# SCH.net
KiCad netlist of a schematic drawn in EasyEDA
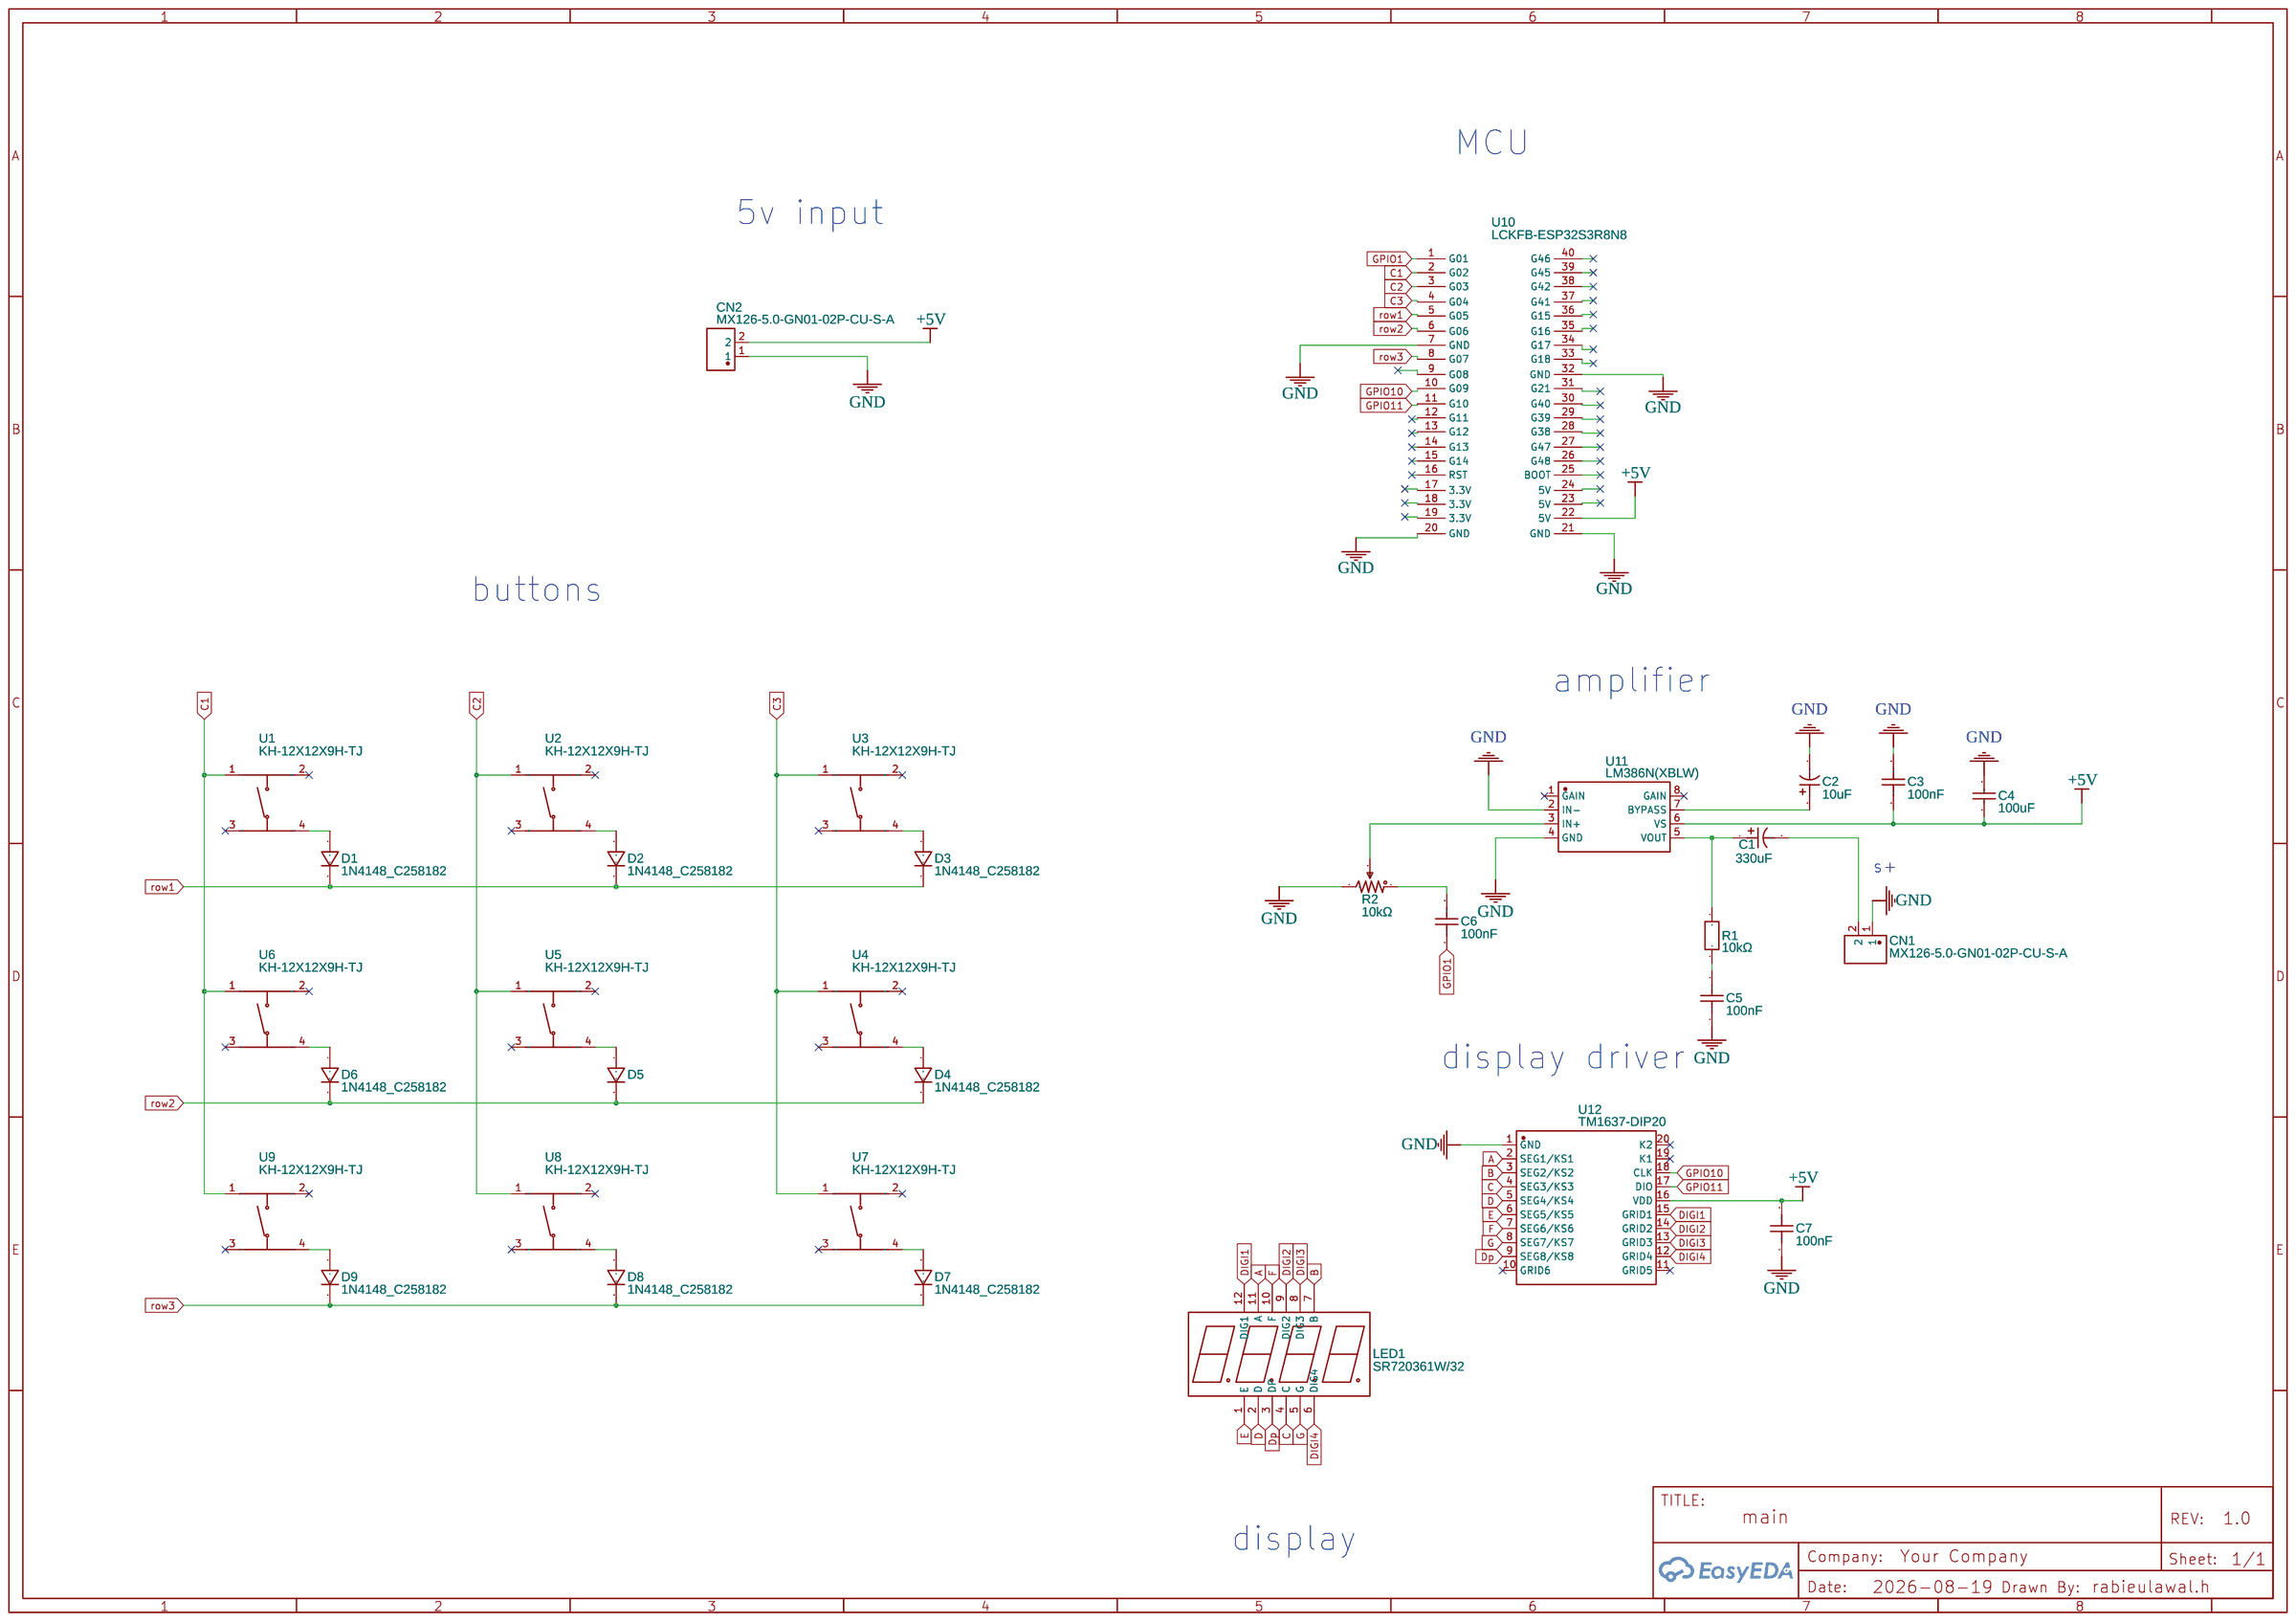
[diagram p0: schematic sheet]

(export (version "E")
  (design (tool "Eeschema 10.0.6"))
  (components
    (comp (ref "C1")
      (value "330uF")
      (fields
        (field (name "Manufacturer Part") "330uF10V6.3x11GF")
        (field (name "Manufacturer") "Econd(米朗电子)")
      )
      (libsource (lib "") (part "330UF10V6.3X11GF"))
    )
    (comp (ref "C2")
      (value "10uF")
      (fields (field (name "Manufacturer Part") "CG100ME511BP") (field (name "Manufacturer") "TWBOR(伯鸿)"))
      (libsource (lib "") (part "CG100ME511BP"))
    )
    (comp (ref "C3")
      (value "100nF")
      (fields (field (name "Manufacturer Part") "FM32X104K101EMG") (field (name "Manufacturer") "PSA(信昌电陶)"))
      (libsource (lib "") (part "FM32X104K101EMG"))
    )
    (comp (ref "C4")
      (value "100uF")
      (fields
        (field (name "Manufacturer Part") "CL32A107MQVNNNE")
        (field (name "Manufacturer") "SAMSUNG(三星)")
      )
      (libsource (lib "") (part "CL32A107MQVNNNE"))
    )
    (comp (ref "C5")
      (value "100nF")
      (fields (field (name "Manufacturer Part") "FM32X104K101EMG") (field (name "Manufacturer") "PSA(信昌电陶)"))
      (libsource (lib "") (part "FM32X104K101EMG"))
    )
    (comp (ref "C6")
      (value "100nF")
      (fields (field (name "Manufacturer Part") "FM32X104K101EMG") (field (name "Manufacturer") "PSA(信昌电陶)"))
      (libsource (lib "") (part "FM32X104K101EMG"))
    )
    (comp (ref "C7")
      (value "100nF")
      (fields (field (name "Manufacturer Part") "FM32X104K101EMG") (field (name "Manufacturer") "PSA(信昌电陶)"))
      (libsource (lib "") (part "FM32X104K101EMG"))
    )
    (comp (ref "CN1")
      (value "MX126-5.0-GN01-02P-CU-S-A")
      (fields
        (field (name "Manufacturer Part") "MX126-5.0-02P-GN01-Cu-S-A")
        (field (name "Manufacturer") "MAX(迈旭)")
      )
      (libsource (lib "") (part "MX126-5.0-GN01-02P-CU-S-A"))
    )
    (comp (ref "CN2")
      (value "MX126-5.0-GN01-02P-CU-S-A")
      (fields
        (field (name "Manufacturer Part") "MX126-5.0-02P-GN01-Cu-S-A")
        (field (name "Manufacturer") "MAX(迈旭)")
      )
      (libsource (lib "") (part "MX126-5.0-GN01-02P-CU-S-A_1"))
    )
    (comp (ref "D1")
      (value "1N4148_C258182")
      (fields (field (name "Manufacturer Part") "1N4148") (field (name "Manufacturer") "onsemi(安森美)"))
      (libsource (lib "") (part "1N4148_C258182"))
    )
    (comp (ref "D2")
      (value "1N4148_C258182")
      (fields (field (name "Manufacturer Part") "1N4148") (field (name "Manufacturer") "onsemi(安森美)"))
      (libsource (lib "") (part "1N4148_C258182"))
    )
    (comp (ref "D3")
      (value "1N4148_C258182")
      (fields (field (name "Manufacturer Part") "1N4148") (field (name "Manufacturer") "onsemi(安森美)"))
      (libsource (lib "") (part "1N4148_C258182"))
    )
    (comp (ref "D4")
      (value "1N4148_C258182")
      (fields (field (name "Manufacturer Part") "1N4148") (field (name "Manufacturer") "onsemi(安森美)"))
      (libsource (lib "") (part "1N4148_C258182"))
    )
    (comp (ref "D5")
      (value "1N4148_C258182")
      (fields (field (name "Manufacturer Part") "1N4148") (field (name "Manufacturer") "onsemi(安森美)"))
      (libsource (lib "") (part "1N4148_C258182"))
    )
    (comp (ref "D6")
      (value "1N4148_C258182")
      (fields (field (name "Manufacturer Part") "1N4148") (field (name "Manufacturer") "onsemi(安森美)"))
      (libsource (lib "") (part "1N4148_C258182"))
    )
    (comp (ref "D7")
      (value "1N4148_C258182")
      (fields (field (name "Manufacturer Part") "1N4148") (field (name "Manufacturer") "onsemi(安森美)"))
      (libsource (lib "") (part "1N4148_C258182"))
    )
    (comp (ref "D8")
      (value "1N4148_C258182")
      (fields (field (name "Manufacturer Part") "1N4148") (field (name "Manufacturer") "onsemi(安森美)"))
      (libsource (lib "") (part "1N4148_C258182"))
    )
    (comp (ref "D9")
      (value "1N4148_C258182")
      (fields (field (name "Manufacturer Part") "1N4148") (field (name "Manufacturer") "onsemi(安森美)"))
      (libsource (lib "") (part "1N4148_C258182"))
    )
    (comp (ref "LED1")
      (value "SR720361W/32")
      (fields (field (name "Manufacturer") "ARKLED(方舟)"))
      (libsource (lib "") (part "SR720361W/32"))
    )
    (comp (ref "R1")
      (value "10kΩ")
      (fields (field (name "Manufacturer Part") "CR1/8W-10K±5%-ST52") (field (name "Manufacturer") "VO(翔胜)"))
      (libsource (lib "") (part "CR1/8W-10K±5%-ST52"))
    )
    (comp (ref "R2")
      (value "10kΩ")
      (fields
        (field (name "Manufacturer Part") "RK09Y11L0001")
        (field (name "Manufacturer") "ALPSALPINE(阿尔卑斯阿尔派)")
      )
      (libsource (lib "") (part "RK09Y11L0001"))
    )
    (comp (ref "U1")
      (value "KH-12X12X9H-TJ")
      (fields (field (name "Manufacturer") "kinghelm(金航标)"))
      (libsource (lib "") (part "KH-12X12X9H-TJ"))
    )
    (comp (ref "U2")
      (value "KH-12X12X9H-TJ")
      (fields (field (name "Manufacturer") "kinghelm(金航标)"))
      (libsource (lib "") (part "KH-12X12X9H-TJ"))
    )
    (comp (ref "U3")
      (value "KH-12X12X9H-TJ")
      (fields (field (name "Manufacturer") "kinghelm(金航标)"))
      (libsource (lib "") (part "KH-12X12X9H-TJ"))
    )
    (comp (ref "U4")
      (value "KH-12X12X9H-TJ")
      (fields (field (name "Manufacturer") "kinghelm(金航标)"))
      (libsource (lib "") (part "KH-12X12X9H-TJ"))
    )
    (comp (ref "U5")
      (value "KH-12X12X9H-TJ")
      (fields (field (name "Manufacturer") "kinghelm(金航标)"))
      (libsource (lib "") (part "KH-12X12X9H-TJ"))
    )
    (comp (ref "U6")
      (value "KH-12X12X9H-TJ")
      (fields (field (name "Manufacturer") "kinghelm(金航标)"))
      (libsource (lib "") (part "KH-12X12X9H-TJ"))
    )
    (comp (ref "U7")
      (value "KH-12X12X9H-TJ")
      (fields (field (name "Manufacturer") "kinghelm(金航标)"))
      (libsource (lib "") (part "KH-12X12X9H-TJ"))
    )
    (comp (ref "U8")
      (value "KH-12X12X9H-TJ")
      (fields (field (name "Manufacturer") "kinghelm(金航标)"))
      (libsource (lib "") (part "KH-12X12X9H-TJ"))
    )
    (comp (ref "U9")
      (value "KH-12X12X9H-TJ")
      (fields (field (name "Manufacturer") "kinghelm(金航标)"))
      (libsource (lib "") (part "KH-12X12X9H-TJ"))
    )
    (comp (ref "U10")
      (value "LCKFB-ESP32S3R8N8")
      (fields (field (name "Manufacturer") "立创开发板"))
      (libsource (lib "") (part "LCKFB-ESP32S3R8N8"))
    )
    (comp (ref "U11")
      (value "LM386N(XBLW)")
      (fields (field (name "Manufacturer") "XBLW(芯伯乐)"))
      (libsource (lib "") (part "LM386N(XBLW)"))
    )
    (comp (ref "U12")
      (value "TM1637-DIP20")
      (fields (field (name "Manufacturer") "TM(天微)"))
      (libsource (lib "") (part "TM1637-DIP20"))
    )
  )
  (nets
    (net (code "1") (name "+5V") (class "Default")
      (node (ref "C3") (pin "1") (pinfunction "1_1") (pintype "unspecified"))
      (node (ref "C4") (pin "1") (pinfunction "1_1") (pintype "input"))
      (node (ref "C7") (pin "2") (pinfunction "2_2") (pintype "unspecified"))
      (node (ref "CN2") (pin "2") (pinfunction "2_2") (pintype "unspecified"))
      (node (ref "U10") (pin "22") (pinfunction "5V_22") (pintype "unspecified"))
      (node (ref "U11") (pin "6") (pinfunction "VS_6") (pintype "unspecified"))
      (node (ref "U12") (pin "16") (pinfunction "VDD_16") (pintype "unspecified"))
    )
    (net (code "2") (name "A") (class "Default")
      (node (ref "LED1") (pin "11") (pinfunction "A_11") (pintype "unspecified"))
      (node (ref "U12") (pin "2") (pinfunction "SEG1/KS1_2") (pintype "unspecified"))
    )
    (net (code "3") (name "B") (class "Default")
      (node (ref "LED1") (pin "7") (pinfunction "B_7") (pintype "unspecified"))
      (node (ref "U12") (pin "3") (pinfunction "SEG2/KS2_3") (pintype "unspecified"))
    )
    (net (code "4") (name "C") (class "Default")
      (node (ref "LED1") (pin "4") (pinfunction "C_4") (pintype "unspecified"))
      (node (ref "U12") (pin "4") (pinfunction "SEG3/KS3_4") (pintype "unspecified"))
    )
    (net (code "5") (name "C1") (class "Default")
      (node (ref "U1") (pin "1") (pinfunction "1_1") (pintype "unspecified"))
      (node (ref "U10") (pin "2") (pinfunction "G02_2") (pintype "unspecified"))
      (node (ref "U6") (pin "1") (pinfunction "1_1") (pintype "unspecified"))
      (node (ref "U9") (pin "1") (pinfunction "1_1") (pintype "unspecified"))
    )
    (net (code "6") (name "C2") (class "Default")
      (node (ref "U10") (pin "3") (pinfunction "G03_3") (pintype "unspecified"))
      (node (ref "U2") (pin "1") (pinfunction "1_1") (pintype "unspecified"))
      (node (ref "U5") (pin "1") (pinfunction "1_1") (pintype "unspecified"))
      (node (ref "U8") (pin "1") (pinfunction "1_1") (pintype "unspecified"))
    )
    (net (code "7") (name "C3") (class "Default")
      (node (ref "U10") (pin "4") (pinfunction "G04_4") (pintype "unspecified"))
      (node (ref "U3") (pin "1") (pinfunction "1_1") (pintype "unspecified"))
      (node (ref "U4") (pin "1") (pinfunction "1_1") (pintype "unspecified"))
      (node (ref "U7") (pin "1") (pinfunction "1_1") (pintype "unspecified"))
    )
    (net (code "8") (name "D") (class "Default")
      (node (ref "LED1") (pin "2") (pinfunction "D_2") (pintype "unspecified"))
      (node (ref "U12") (pin "5") (pinfunction "SEG4/KS4_5") (pintype "unspecified"))
    )
    (net (code "9") (name "DIGI1") (class "Default")
      (node (ref "LED1") (pin "12") (pinfunction "DIG1_12") (pintype "unspecified"))
      (node (ref "U12") (pin "15") (pinfunction "GRID1_15") (pintype "unspecified"))
    )
    (net (code "10") (name "DIGI2") (class "Default")
      (node (ref "LED1") (pin "9") (pinfunction "DIG2_9") (pintype "unspecified"))
      (node (ref "U12") (pin "14") (pinfunction "GRID2_14") (pintype "unspecified"))
    )
    (net (code "11") (name "DIGI3") (class "Default")
      (node (ref "LED1") (pin "8") (pinfunction "DIG3_8") (pintype "unspecified"))
      (node (ref "U12") (pin "13") (pinfunction "GRID3_13") (pintype "unspecified"))
    )
    (net (code "12") (name "DIGI4") (class "Default")
      (node (ref "LED1") (pin "6") (pinfunction "DIG4_6") (pintype "unspecified"))
      (node (ref "U12") (pin "12") (pinfunction "GRID4_12") (pintype "unspecified"))
    )
    (net (code "13") (name "Dp") (class "Default")
      (node (ref "LED1") (pin "3") (pinfunction "DP_3") (pintype "unspecified"))
      (node (ref "U12") (pin "9") (pinfunction "SEG8/KS8_9") (pintype "unspecified"))
    )
    (net (code "14") (name "E") (class "Default")
      (node (ref "LED1") (pin "1") (pinfunction "E_1") (pintype "unspecified"))
      (node (ref "U12") (pin "6") (pinfunction "SEG5/KS5_6") (pintype "unspecified"))
    )
    (net (code "15") (name "F") (class "Default")
      (node (ref "LED1") (pin "10") (pinfunction "F_10") (pintype "unspecified"))
      (node (ref "U12") (pin "7") (pinfunction "SEG6/KS6_7") (pintype "unspecified"))
    )
    (net (code "16") (name "G") (class "Default")
      (node (ref "LED1") (pin "5") (pinfunction "G_5") (pintype "unspecified"))
      (node (ref "U12") (pin "8") (pinfunction "SEG7/KS7_8") (pintype "unspecified"))
    )
    (net (code "17") (name "GND") (class "Default")
      (node (ref "C2") (pin "2") (pinfunction "2_2") (pintype "input"))
      (node (ref "C3") (pin "2") (pinfunction "2_2") (pintype "unspecified"))
      (node (ref "C4") (pin "2") (pinfunction "2_2") (pintype "input"))
      (node (ref "C5") (pin "1") (pinfunction "1_1") (pintype "unspecified"))
      (node (ref "C7") (pin "1") (pinfunction "1_1") (pintype "unspecified"))
      (node (ref "CN1") (pin "1") (pinfunction "1_1") (pintype "unspecified"))
      (node (ref "CN2") (pin "1") (pinfunction "1_1") (pintype "unspecified"))
      (node (ref "R2") (pin "3") (pinfunction "3_3") (pintype "unspecified"))
      (node (ref "U10") (pin "20") (pinfunction "GND_20") (pintype "unspecified"))
      (node (ref "U10") (pin "21") (pinfunction "GND_21") (pintype "unspecified"))
      (node (ref "U10") (pin "32") (pinfunction "GND_32") (pintype "unspecified"))
      (node (ref "U10") (pin "7") (pinfunction "GND_7") (pintype "unspecified"))
      (node (ref "U11") (pin "2") (pinfunction "IN-_2") (pintype "unspecified"))
      (node (ref "U11") (pin "4") (pinfunction "GND_4") (pintype "unspecified"))
      (node (ref "U12") (pin "1") (pinfunction "GND_1") (pintype "unspecified"))
    )
    (net (code "18") (name "GPIO1") (class "Default")
      (node (ref "C6") (pin "1") (pinfunction "1_1") (pintype "unspecified"))
      (node (ref "U10") (pin "1") (pinfunction "G01_1") (pintype "unspecified"))
    )
    (net (code "19") (name "GPIO10") (class "Default")
      (node (ref "U10") (pin "10") (pinfunction "G09_10") (pintype "unspecified"))
      (node (ref "U12") (pin "18") (pinfunction "CLK_18") (pintype "unspecified"))
    )
    (net (code "20") (name "GPIO11") (class "Default")
      (node (ref "U10") (pin "11") (pinfunction "G10_11") (pintype "unspecified"))
      (node (ref "U12") (pin "17") (pinfunction "DIO_17") (pintype "unspecified"))
    )
    (net (code "21") (name "Net-(C1-Pad2)") (class "Default")
      (node (ref "C1") (pin "2") (pinfunction "2_2") (pintype "input"))
      (node (ref "CN1") (pin "2") (pinfunction "2_2") (pintype "unspecified"))
    )
    (net (code "22") (name "Net-(C5-Pad2)") (class "Default")
      (node (ref "C5") (pin "2") (pinfunction "2_2") (pintype "unspecified"))
      (node (ref "R1") (pin "1") (pinfunction "1_1") (pintype "unspecified"))
    )
    (net (code "23") (name "Net-(C6-Pad2)") (class "Default")
      (node (ref "C6") (pin "2") (pinfunction "2_2") (pintype "unspecified"))
      (node (ref "R2") (pin "1") (pinfunction "1_1") (pintype "unspecified"))
    )
    (net (code "24") (name "Net-(D1-A)") (class "Default")
      (node (ref "D1") (pin "1") (pinfunction "A_1") (pintype "unspecified"))
      (node (ref "U1") (pin "4") (pinfunction "4_4") (pintype "unspecified"))
    )
    (net (code "25") (name "Net-(D2-A)") (class "Default")
      (node (ref "D2") (pin "1") (pinfunction "A_1") (pintype "unspecified"))
      (node (ref "U2") (pin "4") (pinfunction "4_4") (pintype "unspecified"))
    )
    (net (code "26") (name "Net-(D3-A)") (class "Default")
      (node (ref "D3") (pin "1") (pinfunction "A_1") (pintype "unspecified"))
      (node (ref "U3") (pin "4") (pinfunction "4_4") (pintype "unspecified"))
    )
    (net (code "27") (name "Net-(D4-A)") (class "Default")
      (node (ref "D4") (pin "1") (pinfunction "A_1") (pintype "unspecified"))
      (node (ref "U4") (pin "4") (pinfunction "4_4") (pintype "unspecified"))
    )
    (net (code "28") (name "Net-(D5-A)") (class "Default")
      (node (ref "D5") (pin "1") (pinfunction "A_1") (pintype "unspecified"))
      (node (ref "U5") (pin "4") (pinfunction "4_4") (pintype "unspecified"))
    )
    (net (code "29") (name "Net-(D6-A)") (class "Default")
      (node (ref "D6") (pin "1") (pinfunction "A_1") (pintype "unspecified"))
      (node (ref "U6") (pin "4") (pinfunction "4_4") (pintype "unspecified"))
    )
    (net (code "30") (name "Net-(D7-A)") (class "Default")
      (node (ref "D7") (pin "1") (pinfunction "A_1") (pintype "unspecified"))
      (node (ref "U7") (pin "4") (pinfunction "4_4") (pintype "unspecified"))
    )
    (net (code "31") (name "Net-(D8-A)") (class "Default")
      (node (ref "D8") (pin "1") (pinfunction "A_1") (pintype "unspecified"))
      (node (ref "U8") (pin "4") (pinfunction "4_4") (pintype "unspecified"))
    )
    (net (code "32") (name "Net-(D9-A)") (class "Default")
      (node (ref "D9") (pin "1") (pinfunction "A_1") (pintype "unspecified"))
      (node (ref "U9") (pin "4") (pinfunction "4_4") (pintype "unspecified"))
    )
    (net (code "33") (name "Net-(U11-BYPASS)") (class "Default")
      (node (ref "C2") (pin "1") (pinfunction "1_1") (pintype "input"))
      (node (ref "U11") (pin "7") (pinfunction "BYPASS_7") (pintype "unspecified"))
    )
    (net (code "34") (name "Net-(U11-IN+)") (class "Default")
      (node (ref "R2") (pin "2") (pinfunction "2_2") (pintype "unspecified"))
      (node (ref "U11") (pin "3") (pinfunction "IN+_3") (pintype "unspecified"))
    )
    (net (code "35") (name "Net-(U11-VOUT)") (class "Default")
      (node (ref "C1") (pin "1") (pinfunction "1_1") (pintype "input"))
      (node (ref "R1") (pin "2") (pinfunction "2_2") (pintype "unspecified"))
      (node (ref "U11") (pin "5") (pinfunction "VOUT_5") (pintype "unspecified"))
    )
    (net (code "36") (name "row1") (class "Default")
      (node (ref "D1") (pin "2") (pinfunction "K_2") (pintype "unspecified"))
      (node (ref "D2") (pin "2") (pinfunction "K_2") (pintype "unspecified"))
      (node (ref "D3") (pin "2") (pinfunction "K_2") (pintype "unspecified"))
      (node (ref "U10") (pin "5") (pinfunction "G05_5") (pintype "unspecified"))
    )
    (net (code "37") (name "row2") (class "Default")
      (node (ref "D4") (pin "2") (pinfunction "K_2") (pintype "unspecified"))
      (node (ref "D5") (pin "2") (pinfunction "K_2") (pintype "unspecified"))
      (node (ref "D6") (pin "2") (pinfunction "K_2") (pintype "unspecified"))
      (node (ref "U10") (pin "6") (pinfunction "G06_6") (pintype "unspecified"))
    )
    (net (code "38") (name "row3") (class "Default")
      (node (ref "D7") (pin "2") (pinfunction "K_2") (pintype "unspecified"))
      (node (ref "D8") (pin "2") (pinfunction "K_2") (pintype "unspecified"))
      (node (ref "D9") (pin "2") (pinfunction "K_2") (pintype "unspecified"))
      (node (ref "U10") (pin "8") (pinfunction "G07_8") (pintype "unspecified"))
    )
    (net (code "39") (name "unconnected-(U1-Pad2)") (class "Default")
      (node (ref "U1") (pin "2") (pinfunction "2_2") (pintype "unspecified+no_connect"))
    )
    (net (code "40") (name "unconnected-(U1-Pad3)") (class "Default")
      (node (ref "U1") (pin "3") (pinfunction "3_3") (pintype "unspecified+no_connect"))
    )
    (net (code "41") (name "unconnected-(U2-Pad2)") (class "Default")
      (node (ref "U2") (pin "2") (pinfunction "2_2") (pintype "unspecified+no_connect"))
    )
    (net (code "42") (name "unconnected-(U2-Pad3)") (class "Default")
      (node (ref "U2") (pin "3") (pinfunction "3_3") (pintype "unspecified+no_connect"))
    )
    (net (code "43") (name "unconnected-(U3-Pad2)") (class "Default")
      (node (ref "U3") (pin "2") (pinfunction "2_2") (pintype "unspecified+no_connect"))
    )
    (net (code "44") (name "unconnected-(U3-Pad3)") (class "Default")
      (node (ref "U3") (pin "3") (pinfunction "3_3") (pintype "unspecified+no_connect"))
    )
    (net (code "45") (name "unconnected-(U4-Pad2)") (class "Default")
      (node (ref "U4") (pin "2") (pinfunction "2_2") (pintype "unspecified+no_connect"))
    )
    (net (code "46") (name "unconnected-(U4-Pad3)") (class "Default")
      (node (ref "U4") (pin "3") (pinfunction "3_3") (pintype "unspecified+no_connect"))
    )
    (net (code "47") (name "unconnected-(U5-Pad2)") (class "Default")
      (node (ref "U5") (pin "2") (pinfunction "2_2") (pintype "unspecified+no_connect"))
    )
    (net (code "48") (name "unconnected-(U5-Pad3)") (class "Default")
      (node (ref "U5") (pin "3") (pinfunction "3_3") (pintype "unspecified+no_connect"))
    )
    (net (code "49") (name "unconnected-(U6-Pad2)") (class "Default")
      (node (ref "U6") (pin "2") (pinfunction "2_2") (pintype "unspecified+no_connect"))
    )
    (net (code "50") (name "unconnected-(U6-Pad3)") (class "Default")
      (node (ref "U6") (pin "3") (pinfunction "3_3") (pintype "unspecified+no_connect"))
    )
    (net (code "51") (name "unconnected-(U7-Pad2)") (class "Default")
      (node (ref "U7") (pin "2") (pinfunction "2_2") (pintype "unspecified+no_connect"))
    )
    (net (code "52") (name "unconnected-(U7-Pad3)") (class "Default")
      (node (ref "U7") (pin "3") (pinfunction "3_3") (pintype "unspecified+no_connect"))
    )
    (net (code "53") (name "unconnected-(U8-Pad2)") (class "Default")
      (node (ref "U8") (pin "2") (pinfunction "2_2") (pintype "unspecified+no_connect"))
    )
    (net (code "54") (name "unconnected-(U8-Pad3)") (class "Default")
      (node (ref "U8") (pin "3") (pinfunction "3_3") (pintype "unspecified+no_connect"))
    )
    (net (code "55") (name "unconnected-(U9-Pad2)") (class "Default")
      (node (ref "U9") (pin "2") (pinfunction "2_2") (pintype "unspecified+no_connect"))
    )
    (net (code "56") (name "unconnected-(U9-Pad3)") (class "Default")
      (node (ref "U9") (pin "3") (pinfunction "3_3") (pintype "unspecified+no_connect"))
    )
    (net (code "57") (name "unconnected-(U10-3.3V-Pad17)") (class "Default")
      (node (ref "U10") (pin "17") (pinfunction "3.3V_17") (pintype "unspecified+no_connect"))
    )
    (net (code "58") (name "unconnected-(U10-3.3V-Pad18)") (class "Default")
      (node (ref "U10") (pin "18") (pinfunction "3.3V_18") (pintype "unspecified+no_connect"))
    )
    (net (code "59") (name "unconnected-(U10-3.3V-Pad19)") (class "Default")
      (node (ref "U10") (pin "19") (pinfunction "3.3V_19") (pintype "unspecified+no_connect"))
    )
    (net (code "60") (name "unconnected-(U10-5V-Pad23)") (class "Default")
      (node (ref "U10") (pin "23") (pinfunction "5V_23") (pintype "unspecified+no_connect"))
    )
    (net (code "61") (name "unconnected-(U10-5V-Pad24)") (class "Default")
      (node (ref "U10") (pin "24") (pinfunction "5V_24") (pintype "unspecified+no_connect"))
    )
    (net (code "62") (name "unconnected-(U10-BOOT-Pad25)") (class "Default")
      (node (ref "U10") (pin "25") (pinfunction "BOOT_25") (pintype "unspecified+no_connect"))
    )
    (net (code "63") (name "unconnected-(U10-G08-Pad9)") (class "Default")
      (node (ref "U10") (pin "9") (pinfunction "G08_9") (pintype "unspecified+no_connect"))
    )
    (net (code "64") (name "unconnected-(U10-G11-Pad12)") (class "Default")
      (node (ref "U10") (pin "12") (pinfunction "G11_12") (pintype "unspecified+no_connect"))
    )
    (net (code "65") (name "unconnected-(U10-G12-Pad13)") (class "Default")
      (node (ref "U10") (pin "13") (pinfunction "G12_13") (pintype "unspecified+no_connect"))
    )
    (net (code "66") (name "unconnected-(U10-G13-Pad14)") (class "Default")
      (node (ref "U10") (pin "14") (pinfunction "G13_14") (pintype "unspecified+no_connect"))
    )
    (net (code "67") (name "unconnected-(U10-G14-Pad15)") (class "Default")
      (node (ref "U10") (pin "15") (pinfunction "G14_15") (pintype "unspecified+no_connect"))
    )
    (net (code "68") (name "unconnected-(U10-G15-Pad36)") (class "Default")
      (node (ref "U10") (pin "36") (pinfunction "G15_36") (pintype "unspecified+no_connect"))
    )
    (net (code "69") (name "unconnected-(U10-G16-Pad35)") (class "Default")
      (node (ref "U10") (pin "35") (pinfunction "G16_35") (pintype "unspecified+no_connect"))
    )
    (net (code "70") (name "unconnected-(U10-G17-Pad34)") (class "Default")
      (node (ref "U10") (pin "34") (pinfunction "G17_34") (pintype "unspecified+no_connect"))
    )
    (net (code "71") (name "unconnected-(U10-G18-Pad33)") (class "Default")
      (node (ref "U10") (pin "33") (pinfunction "G18_33") (pintype "unspecified+no_connect"))
    )
    (net (code "72") (name "unconnected-(U10-G21-Pad31)") (class "Default")
      (node (ref "U10") (pin "31") (pinfunction "G21_31") (pintype "unspecified+no_connect"))
    )
    (net (code "73") (name "unconnected-(U10-G38-Pad28)") (class "Default")
      (node (ref "U10") (pin "28") (pinfunction "G38_28") (pintype "unspecified+no_connect"))
    )
    (net (code "74") (name "unconnected-(U10-G39-Pad29)") (class "Default")
      (node (ref "U10") (pin "29") (pinfunction "G39_29") (pintype "unspecified+no_connect"))
    )
    (net (code "75") (name "unconnected-(U10-G40-Pad30)") (class "Default")
      (node (ref "U10") (pin "30") (pinfunction "G40_30") (pintype "unspecified+no_connect"))
    )
    (net (code "76") (name "unconnected-(U10-G41-Pad37)") (class "Default")
      (node (ref "U10") (pin "37") (pinfunction "G41_37") (pintype "unspecified+no_connect"))
    )
    (net (code "77") (name "unconnected-(U10-G42-Pad38)") (class "Default")
      (node (ref "U10") (pin "38") (pinfunction "G42_38") (pintype "unspecified+no_connect"))
    )
    (net (code "78") (name "unconnected-(U10-G45-Pad39)") (class "Default")
      (node (ref "U10") (pin "39") (pinfunction "G45_39") (pintype "unspecified+no_connect"))
    )
    (net (code "79") (name "unconnected-(U10-G46-Pad40)") (class "Default")
      (node (ref "U10") (pin "40") (pinfunction "G46_40") (pintype "unspecified+no_connect"))
    )
    (net (code "80") (name "unconnected-(U10-G47-Pad27)") (class "Default")
      (node (ref "U10") (pin "27") (pinfunction "G47_27") (pintype "unspecified+no_connect"))
    )
    (net (code "81") (name "unconnected-(U10-G48-Pad26)") (class "Default")
      (node (ref "U10") (pin "26") (pinfunction "G48_26") (pintype "unspecified+no_connect"))
    )
    (net (code "82") (name "unconnected-(U10-RST-Pad16)") (class "Default")
      (node (ref "U10") (pin "16") (pinfunction "RST_16") (pintype "unspecified+no_connect"))
    )
    (net (code "83") (name "unconnected-(U11-GAIN-Pad1)") (class "Default")
      (node (ref "U11") (pin "1") (pinfunction "GAIN_1") (pintype "unspecified+no_connect"))
    )
    (net (code "84") (name "unconnected-(U11-GAIN-Pad8)") (class "Default")
      (node (ref "U11") (pin "8") (pinfunction "GAIN_8") (pintype "unspecified+no_connect"))
    )
    (net (code "85") (name "unconnected-(U12-GRID5-Pad11)") (class "Default")
      (node (ref "U12") (pin "11") (pinfunction "GRID5_11") (pintype "unspecified+no_connect"))
    )
    (net (code "86") (name "unconnected-(U12-GRID6-Pad10)") (class "Default")
      (node (ref "U12") (pin "10") (pinfunction "GRID6_10") (pintype "unspecified+no_connect"))
    )
    (net (code "87") (name "unconnected-(U12-K1-Pad19)") (class "Default")
      (node (ref "U12") (pin "19") (pinfunction "K1_19") (pintype "unspecified+no_connect"))
    )
    (net (code "88") (name "unconnected-(U12-K2-Pad20)") (class "Default")
      (node (ref "U12") (pin "20") (pinfunction "K2_20") (pintype "unspecified+no_connect"))
    )
  )
)
